# continuity_tester.net
KiCad netlist of a schematic drawn in EAGLE
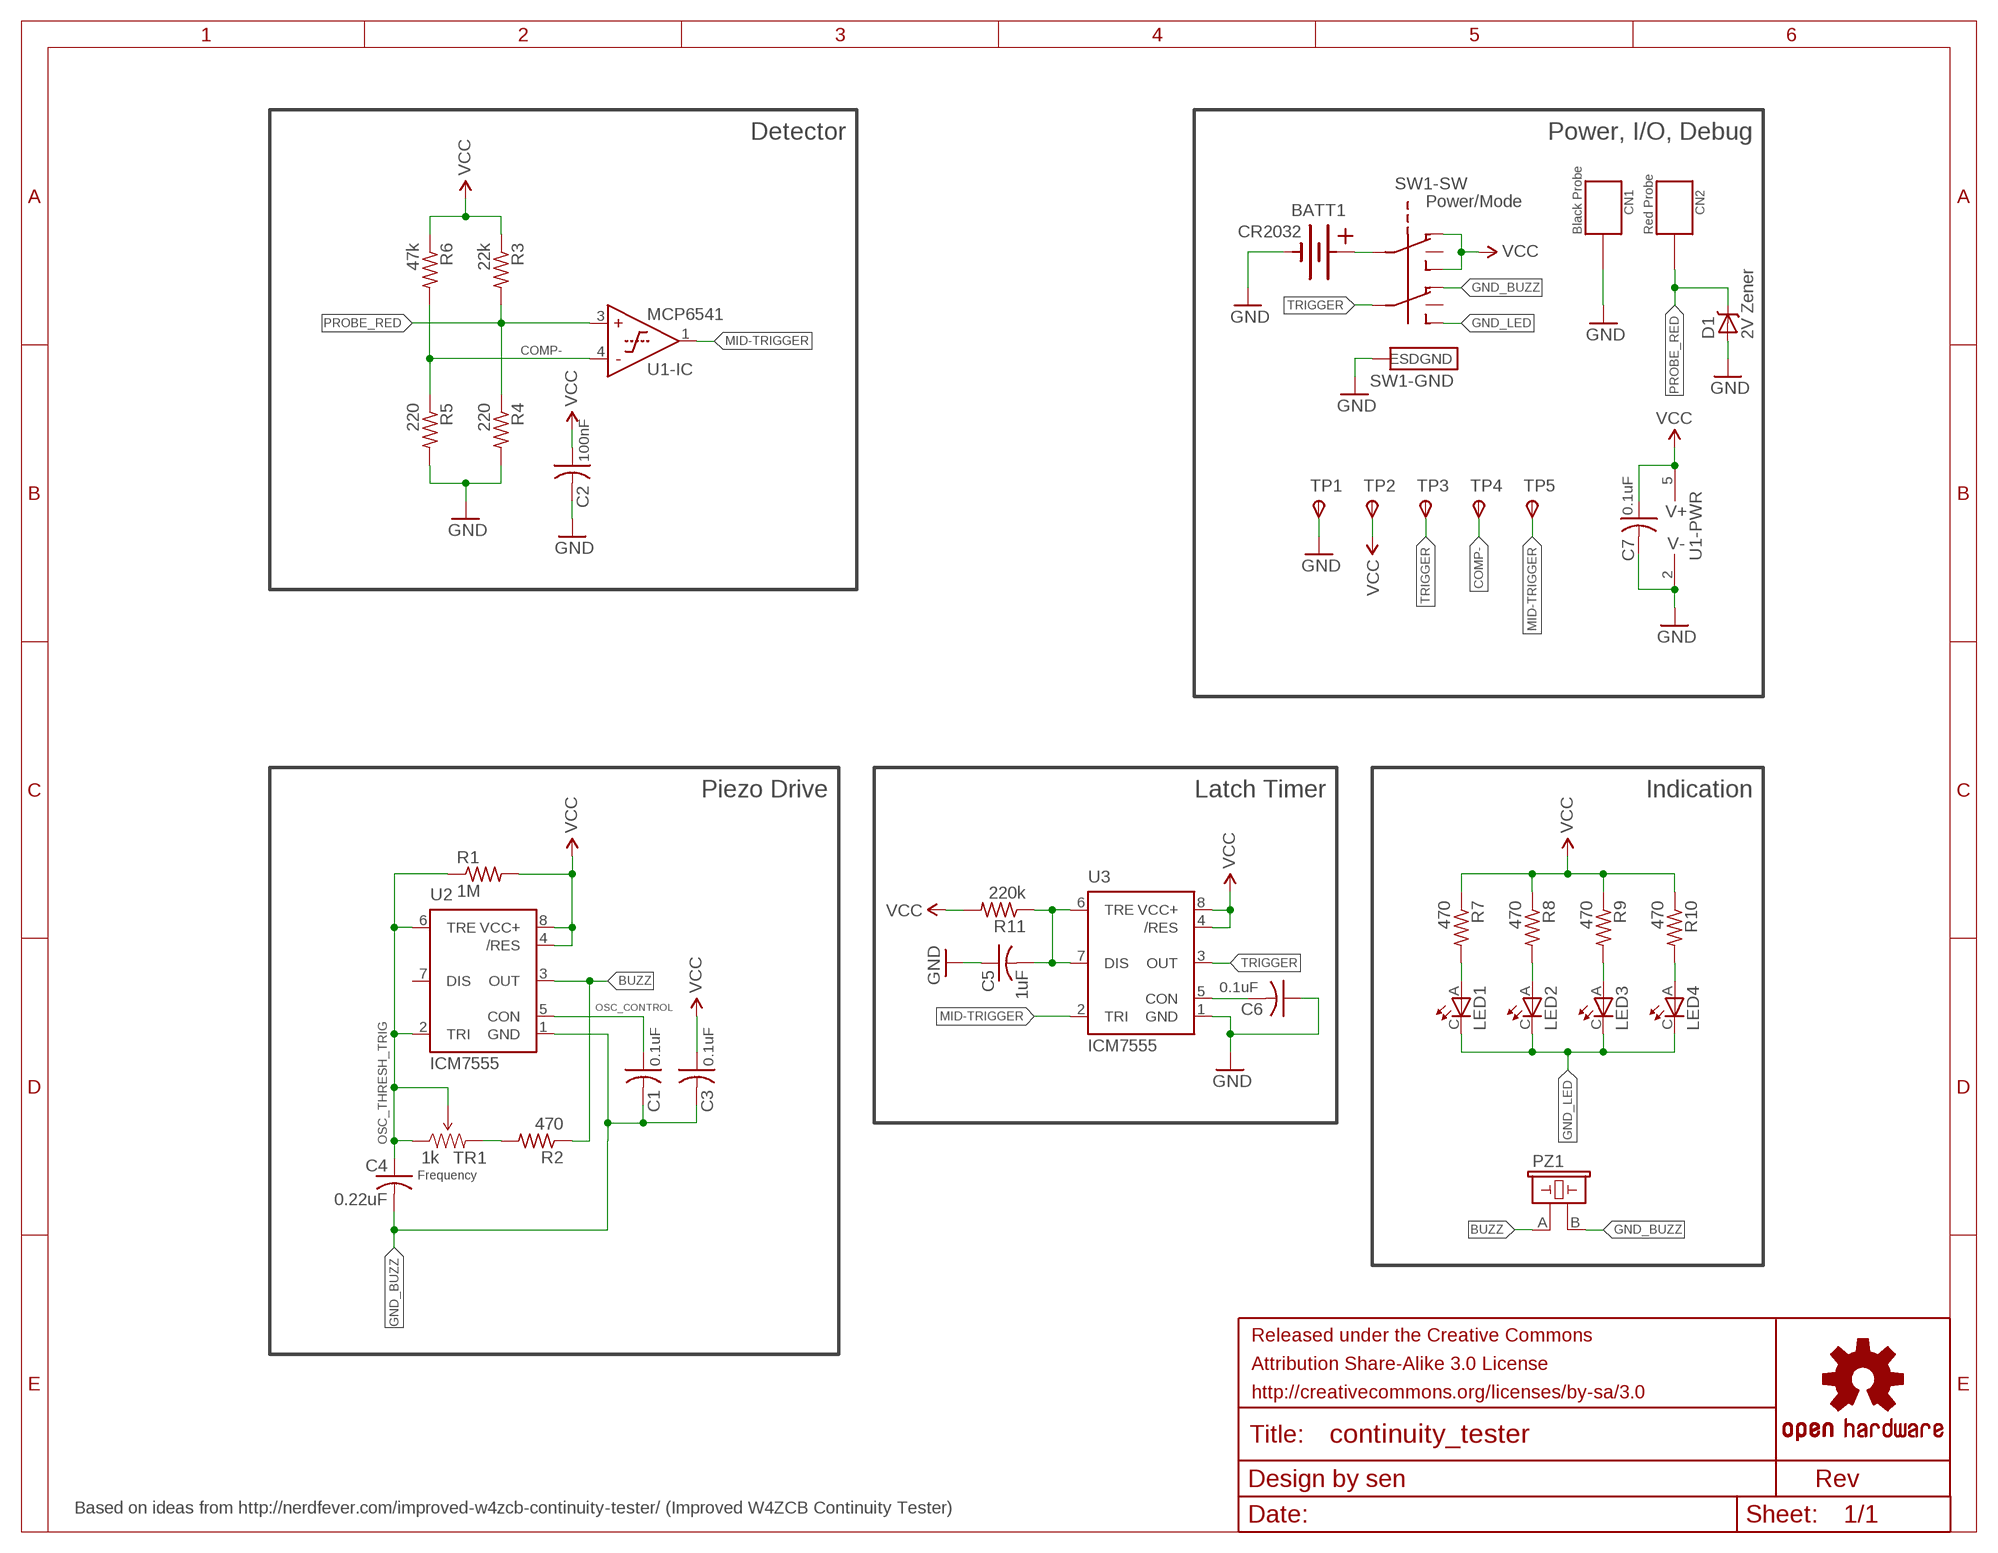
[diagram p0: schematic, sheet 1]

(export (version "E")
  (design (tool "Eeschema 10.0.6"))
  (components
    (comp (ref "BATT1")
      (value "CR2032")
      (footprint "eagle-import:BK-912-CR2032")
      (libsource (lib "eagle-import") (part "CR2032"))
    )
    (comp (ref "C1")
      (value "0.1uF")
      (footprint "eagle-import:C0603")
      (libsource (lib "eagle-import") (part "C-USC0603"))
    )
    (comp (ref "C2")
      (value "100nF")
      (footprint "eagle-import:C0603")
      (libsource (lib "eagle-import") (part "C-USC0603"))
    )
    (comp (ref "C3")
      (value "0.1uF")
      (footprint "eagle-import:C0603")
      (libsource (lib "eagle-import") (part "C-USC0603"))
    )
    (comp (ref "C4")
      (value "0.22uF")
      (footprint "eagle-import:C0603")
      (libsource (lib "eagle-import") (part "C-USC0603"))
    )
    (comp (ref "C5")
      (value "1uF")
      (footprint "eagle-import:C0603")
      (libsource (lib "eagle-import") (part "C-USC0603"))
    )
    (comp (ref "C6")
      (value "0.1uF")
      (footprint "eagle-import:C0603")
      (libsource (lib "eagle-import") (part "C-USC0603"))
    )
    (comp (ref "C7")
      (value "0.1uF")
      (footprint "eagle-import:C0603")
      (libsource (lib "eagle-import") (part "C-USC0603"))
    )
    (comp (ref "CN1")
      (value "Black Probe")
      (footprint "eagle-import:CALTEST-CT3151")
      (libsource (lib "eagle-import") (part "CALTEST-CT3151"))
    )
    (comp (ref "CN2")
      (value "Red Probe")
      (footprint "eagle-import:CALTEST-CT3151")
      (libsource (lib "eagle-import") (part "CALTEST-CT3151"))
    )
    (comp (ref "D1")
      (value "2V Zener")
      (footprint "eagle-import:DO-219AC")
      (libsource (lib "eagle-import") (part "ZENER"))
    )
    (comp (ref "FRAME1")
      (value "FRAME-LETTER-GRID-OSHW-SENOSHW-LOGO-L")
      (footprint "eagle-import:OSHW-LOGO-L")
      (fields (field (name "REV") "002"))
      (libsource (lib "eagle-import") (part "FRAME-LETTER-GRID-OSHW-SENOSHW-LOGO-L"))
    )
    (comp (ref "LED1")
      (value "LITEON-LTST020")
      (footprint "eagle-import:LITEON-LTST020")
      (libsource (lib "eagle-import") (part "LITEON-LTST020"))
    )
    (comp (ref "LED2")
      (value "LITEON-LTST020")
      (footprint "eagle-import:LITEON-LTST020")
      (libsource (lib "eagle-import") (part "LITEON-LTST020"))
    )
    (comp (ref "LED3")
      (value "LITEON-LTST020")
      (footprint "eagle-import:LITEON-LTST020")
      (libsource (lib "eagle-import") (part "LITEON-LTST020"))
    )
    (comp (ref "LED4")
      (value "LITEON-LTST020")
      (footprint "eagle-import:LITEON-LTST020")
      (libsource (lib "eagle-import") (part "LITEON-LTST020"))
    )
    (comp (ref "PZ1")
      (value "MURATA-PKMCS0909")
      (footprint "eagle-import:MURATA-PKMCS0909")
      (libsource (lib "eagle-import") (part "MURATA-PKMCS0909"))
    )
    (comp (ref "R1")
      (value "1M")
      (footprint "eagle-import:R0603")
      (libsource (lib "eagle-import") (part "R-US_R0603"))
    )
    (comp (ref "R2")
      (value "470")
      (footprint "eagle-import:R0603")
      (libsource (lib "eagle-import") (part "R-US_R0603"))
    )
    (comp (ref "R3")
      (value "22k")
      (footprint "eagle-import:R0603")
      (libsource (lib "eagle-import") (part "R-US_R0603"))
    )
    (comp (ref "R4")
      (value "220")
      (footprint "eagle-import:R0603")
      (libsource (lib "eagle-import") (part "R-US_R0603"))
    )
    (comp (ref "R5")
      (value "220")
      (footprint "eagle-import:R0603")
      (libsource (lib "eagle-import") (part "R-US_R0603"))
    )
    (comp (ref "R6")
      (value "47k")
      (footprint "eagle-import:R0603")
      (libsource (lib "eagle-import") (part "R-US_R0603"))
    )
    (comp (ref "R7")
      (value "470")
      (footprint "eagle-import:R0603")
      (libsource (lib "eagle-import") (part "R-US_R0603"))
    )
    (comp (ref "R8")
      (value "470")
      (footprint "eagle-import:R0603")
      (libsource (lib "eagle-import") (part "R-US_R0603"))
    )
    (comp (ref "R9")
      (value "470")
      (footprint "eagle-import:R0603")
      (libsource (lib "eagle-import") (part "R-US_R0603"))
    )
    (comp (ref "R10")
      (value "470")
      (footprint "eagle-import:R0603")
      (libsource (lib "eagle-import") (part "R-US_R0603"))
    )
    (comp (ref "R11")
      (value "220k")
      (footprint "eagle-import:R0603")
      (libsource (lib "eagle-import") (part "R-US_R0603"))
    )
    (comp (ref "SW1")
      (value "Power/Mode")
      (footprint "eagle-import:ESWITCH-EG2308")
      (libsource (lib "eagle-import") (part "ESWITCH-EG2308"))
    )
    (comp (ref "TP1")
      (value "GND")
      (footprint "eagle-import:B1,27")
      (libsource (lib "eagle-import") (part "TPSB1,27"))
    )
    (comp (ref "TP2")
      (value "VCC")
      (footprint "eagle-import:B1,27")
      (libsource (lib "eagle-import") (part "TPSB1,27"))
    )
    (comp (ref "TP3")
      (value "TRIGGER")
      (footprint "eagle-import:B1,27")
      (libsource (lib "eagle-import") (part "TPSB1,27"))
    )
    (comp (ref "TP4")
      (value "COMP-")
      (footprint "eagle-import:B1,27")
      (libsource (lib "eagle-import") (part "TPSB1,27"))
    )
    (comp (ref "TP5")
      (value "MID-TRIGGER")
      (footprint "eagle-import:B1,27")
      (libsource (lib "eagle-import") (part "TPSB1,27"))
    )
    (comp (ref "TR1")
      (value "1k")
      (footprint "eagle-import:NIDEC-ST4EA")
      (libsource (lib "eagle-import") (part "NIDEC-ST4EA"))
    )
    (comp (ref "U1")
      (value "MCP6541")
      (footprint "eagle-import:SOT23-5")
      (libsource (lib "eagle-import") (part "MCP6541"))
    )
    (comp (ref "U2")
      (value "ICM7555")
      (footprint "eagle-import:SO08")
      (libsource (lib "eagle-import") (part "NE555D"))
    )
    (comp (ref "U3")
      (value "ICM7555")
      (footprint "eagle-import:SO08")
      (libsource (lib "eagle-import") (part "NE555D"))
    )
  )
  (nets
    (net (code "1") (name "/OSC_CONTROL") (class "Default")
      (node (ref "C1") (pin "1") (pinfunction "1_1") (pintype "passive"))
      (node (ref "U2") (pin "5") (pinfunction "CON_5") (pintype "input"))
    )
    (net (code "2") (name "/OSC_THRESH_TRIG") (class "Default")
      (node (ref "C4") (pin "1") (pinfunction "1_1") (pintype "passive"))
      (node (ref "R1") (pin "1") (pinfunction "1_1") (pintype "passive"))
      (node (ref "TR1") (pin "CCW") (pinfunction "CCW_CCW") (pintype "passive"))
      (node (ref "TR1") (pin "WIPER") (pinfunction "WIPER_WIPER") (pintype "passive"))
      (node (ref "U2") (pin "2") (pinfunction "TRI_2") (pintype "input"))
      (node (ref "U2") (pin "6") (pinfunction "TRE_6") (pintype "input"))
    )
    (net (code "3") (name "BUZZ") (class "Default")
      (node (ref "PZ1") (pin "A") (pinfunction "1_A") (pintype "passive"))
      (node (ref "R2") (pin "1") (pinfunction "1_1") (pintype "passive"))
      (node (ref "U2") (pin "3") (pinfunction "OUT_3") (pintype "output"))
    )
    (net (code "4") (name "COMP-") (class "Default")
      (node (ref "R5") (pin "1") (pinfunction "1_1") (pintype "passive"))
      (node (ref "R6") (pin "2") (pinfunction "2_2") (pintype "passive"))
      (node (ref "TP4") (pin "TP") (pinfunction "PP_TP") (pintype "input"))
      (node (ref "U1") (pin "4") (pinfunction "IN-_4") (pintype "input"))
    )
    (net (code "5") (name "GND") (class "Default")
      (node (ref "BATT1") (pin "-") (pinfunction "-1_-") (pintype "power_in"))
      (node (ref "C2") (pin "2") (pinfunction "2_2") (pintype "passive"))
      (node (ref "C5") (pin "1") (pinfunction "1_1") (pintype "passive"))
      (node (ref "C6") (pin "1") (pinfunction "1_1") (pintype "passive"))
      (node (ref "C7") (pin "2") (pinfunction "2_2") (pintype "passive"))
      (node (ref "CN1") (pin "A") (pinfunction "P$1_A") (pintype "passive"))
      (node (ref "CN1") (pin "B") (pinfunction "P$1_B") (pintype "passive"))
      (node (ref "CN1") (pin "C") (pinfunction "P$1_C") (pintype "passive"))
      (node (ref "CN1") (pin "D") (pinfunction "P$1_D") (pintype "passive"))
      (node (ref "D1") (pin "A") (pinfunction "A_A") (pintype "passive"))
      (node (ref "R4") (pin "2") (pinfunction "2_2") (pintype "passive"))
      (node (ref "R5") (pin "2") (pinfunction "2_2") (pintype "passive"))
      (node (ref "SW1") (pin "SUPPORT1") (pinfunction "ESDGND_SUPPORT1") (pintype "passive"))
      (node (ref "SW1") (pin "SUPPORT2") (pinfunction "ESDGND_SUPPORT2") (pintype "passive"))
      (node (ref "TP1") (pin "TP") (pinfunction "PP_TP") (pintype "input"))
      (node (ref "U1") (pin "2") (pinfunction "V-_2") (pintype "power_in"))
      (node (ref "U3") (pin "1") (pinfunction "GND_1") (pintype "power_in"))
    )
    (net (code "6") (name "GND_BUZZ") (class "Default")
      (node (ref "C1") (pin "2") (pinfunction "2_2") (pintype "passive"))
      (node (ref "C3") (pin "2") (pinfunction "2_2") (pintype "passive"))
      (node (ref "C4") (pin "2") (pinfunction "2_2") (pintype "passive"))
      (node (ref "PZ1") (pin "B") (pinfunction "2_B") (pintype "passive"))
      (node (ref "SW1") (pin "5") (pinfunction "2A_5") (pintype "passive"))
      (node (ref "U2") (pin "1") (pinfunction "GND_1") (pintype "power_in"))
    )
    (net (code "7") (name "GND_LED") (class "Default")
      (node (ref "LED1") (pin "C") (pinfunction "C_C") (pintype "passive"))
      (node (ref "LED2") (pin "C") (pinfunction "C_C") (pintype "passive"))
      (node (ref "LED3") (pin "C") (pinfunction "C_C") (pintype "passive"))
      (node (ref "LED4") (pin "C") (pinfunction "C_C") (pintype "passive"))
      (node (ref "SW1") (pin "8") (pinfunction "2C_8") (pintype "passive"))
    )
    (net (code "8") (name "MID-TRIGGER") (class "Default")
      (node (ref "TP5") (pin "TP") (pinfunction "PP_TP") (pintype "input"))
      (node (ref "U1") (pin "1") (pinfunction "OUT_1") (pintype "output"))
      (node (ref "U3") (pin "2") (pinfunction "TRI_2") (pintype "input"))
    )
    (net (code "9") (name "Net-(BATT1-+2)") (class "Default")
      (node (ref "BATT1") (pin "+1") (pinfunction "+2_+1") (pintype "power_in"))
      (node (ref "SW1") (pin "3") (pinfunction "1_3") (pintype "passive"))
    )
    (net (code "10") (name "Net-(LED1-PadA)") (class "Default")
      (node (ref "LED1") (pin "A") (pinfunction "A_A") (pintype "passive"))
      (node (ref "R7") (pin "2") (pinfunction "2_2") (pintype "passive"))
    )
    (net (code "11") (name "Net-(LED2-PadA)") (class "Default")
      (node (ref "LED2") (pin "A") (pinfunction "A_A") (pintype "passive"))
      (node (ref "R8") (pin "2") (pinfunction "2_2") (pintype "passive"))
    )
    (net (code "12") (name "Net-(LED3-PadA)") (class "Default")
      (node (ref "LED3") (pin "A") (pinfunction "A_A") (pintype "passive"))
      (node (ref "R9") (pin "2") (pinfunction "2_2") (pintype "passive"))
    )
    (net (code "13") (name "Net-(LED4-PadA)") (class "Default")
      (node (ref "LED4") (pin "A") (pinfunction "A_A") (pintype "passive"))
      (node (ref "R10") (pin "2") (pinfunction "2_2") (pintype "passive"))
    )
    (net (code "14") (name "Net-(R2-Pad2)") (class "Default")
      (node (ref "R2") (pin "2") (pinfunction "2_2") (pintype "passive"))
      (node (ref "TR1") (pin "CW") (pinfunction "CW_CW") (pintype "passive"))
    )
    (net (code "15") (name "Net-(U3-CON)") (class "Default")
      (node (ref "C6") (pin "2") (pinfunction "2_2") (pintype "passive"))
      (node (ref "U3") (pin "5") (pinfunction "CON_5") (pintype "input"))
    )
    (net (code "16") (name "Net-(U3-DIS)") (class "Default")
      (node (ref "C5") (pin "2") (pinfunction "2_2") (pintype "passive"))
      (node (ref "R11") (pin "1") (pinfunction "1_1") (pintype "passive"))
      (node (ref "U3") (pin "6") (pinfunction "TRE_6") (pintype "input"))
      (node (ref "U3") (pin "7") (pinfunction "DIS_7") (pintype "input"))
    )
    (net (code "17") (name "PROBE_RED") (class "Default")
      (node (ref "CN2") (pin "A") (pinfunction "P$1_A") (pintype "passive"))
      (node (ref "CN2") (pin "B") (pinfunction "P$1_B") (pintype "passive"))
      (node (ref "CN2") (pin "C") (pinfunction "P$1_C") (pintype "passive"))
      (node (ref "CN2") (pin "D") (pinfunction "P$1_D") (pintype "passive"))
      (node (ref "D1") (pin "K") (pinfunction "C_K") (pintype "passive"))
      (node (ref "R3") (pin "2") (pinfunction "2_2") (pintype "passive"))
      (node (ref "R4") (pin "1") (pinfunction "1_1") (pintype "passive"))
      (node (ref "U1") (pin "3") (pinfunction "IN+_3") (pintype "input"))
    )
    (net (code "18") (name "TRIGGER") (class "Default")
      (node (ref "SW1") (pin "7") (pinfunction "2_7") (pintype "passive"))
      (node (ref "TP3") (pin "TP") (pinfunction "PP_TP") (pintype "input"))
      (node (ref "U3") (pin "3") (pinfunction "OUT_3") (pintype "output"))
    )
    (net (code "19") (name "VCC") (class "Default")
      (node (ref "C2") (pin "1") (pinfunction "1_1") (pintype "passive"))
      (node (ref "C3") (pin "1") (pinfunction "1_1") (pintype "passive"))
      (node (ref "C7") (pin "1") (pinfunction "1_1") (pintype "passive"))
      (node (ref "R1") (pin "2") (pinfunction "2_2") (pintype "passive"))
      (node (ref "R10") (pin "1") (pinfunction "1_1") (pintype "passive"))
      (node (ref "R11") (pin "2") (pinfunction "2_2") (pintype "passive"))
      (node (ref "R3") (pin "1") (pinfunction "1_1") (pintype "passive"))
      (node (ref "R6") (pin "1") (pinfunction "1_1") (pintype "passive"))
      (node (ref "R7") (pin "1") (pinfunction "1_1") (pintype "passive"))
      (node (ref "R8") (pin "1") (pinfunction "1_1") (pintype "passive"))
      (node (ref "R9") (pin "1") (pinfunction "1_1") (pintype "passive"))
      (node (ref "SW1") (pin "1") (pinfunction "1A_1") (pintype "passive"))
      (node (ref "SW1") (pin "4") (pinfunction "1C_4") (pintype "passive"))
      (node (ref "TP2") (pin "TP") (pinfunction "PP_TP") (pintype "input"))
      (node (ref "U1") (pin "5") (pinfunction "V+_5") (pintype "power_in"))
      (node (ref "U2") (pin "4") (pinfunction "/RES_4") (pintype "input"))
      (node (ref "U2") (pin "8") (pinfunction "VCC+_8") (pintype "power_in"))
      (node (ref "U3") (pin "4") (pinfunction "/RES_4") (pintype "input"))
      (node (ref "U3") (pin "8") (pinfunction "VCC+_8") (pintype "power_in"))
    )
    (net (code "20") (name "unconnected-(SW1B-1B-Pad2)") (class "Default")
      (node (ref "SW1") (pin "2") (pinfunction "1B_2") (pintype "passive"))
    )
    (net (code "21") (name "unconnected-(SW1B-2B-Pad6)") (class "Default")
      (node (ref "SW1") (pin "6") (pinfunction "2B_6") (pintype "passive"))
    )
    (net (code "22") (name "unconnected-(U2-DIS-Pad7)") (class "Default")
      (node (ref "U2") (pin "7") (pinfunction "DIS_7") (pintype "input"))
    )
  )
)
